# emergency-button.net
KiCad netlist of a schematic drawn in EasyEDA Pro
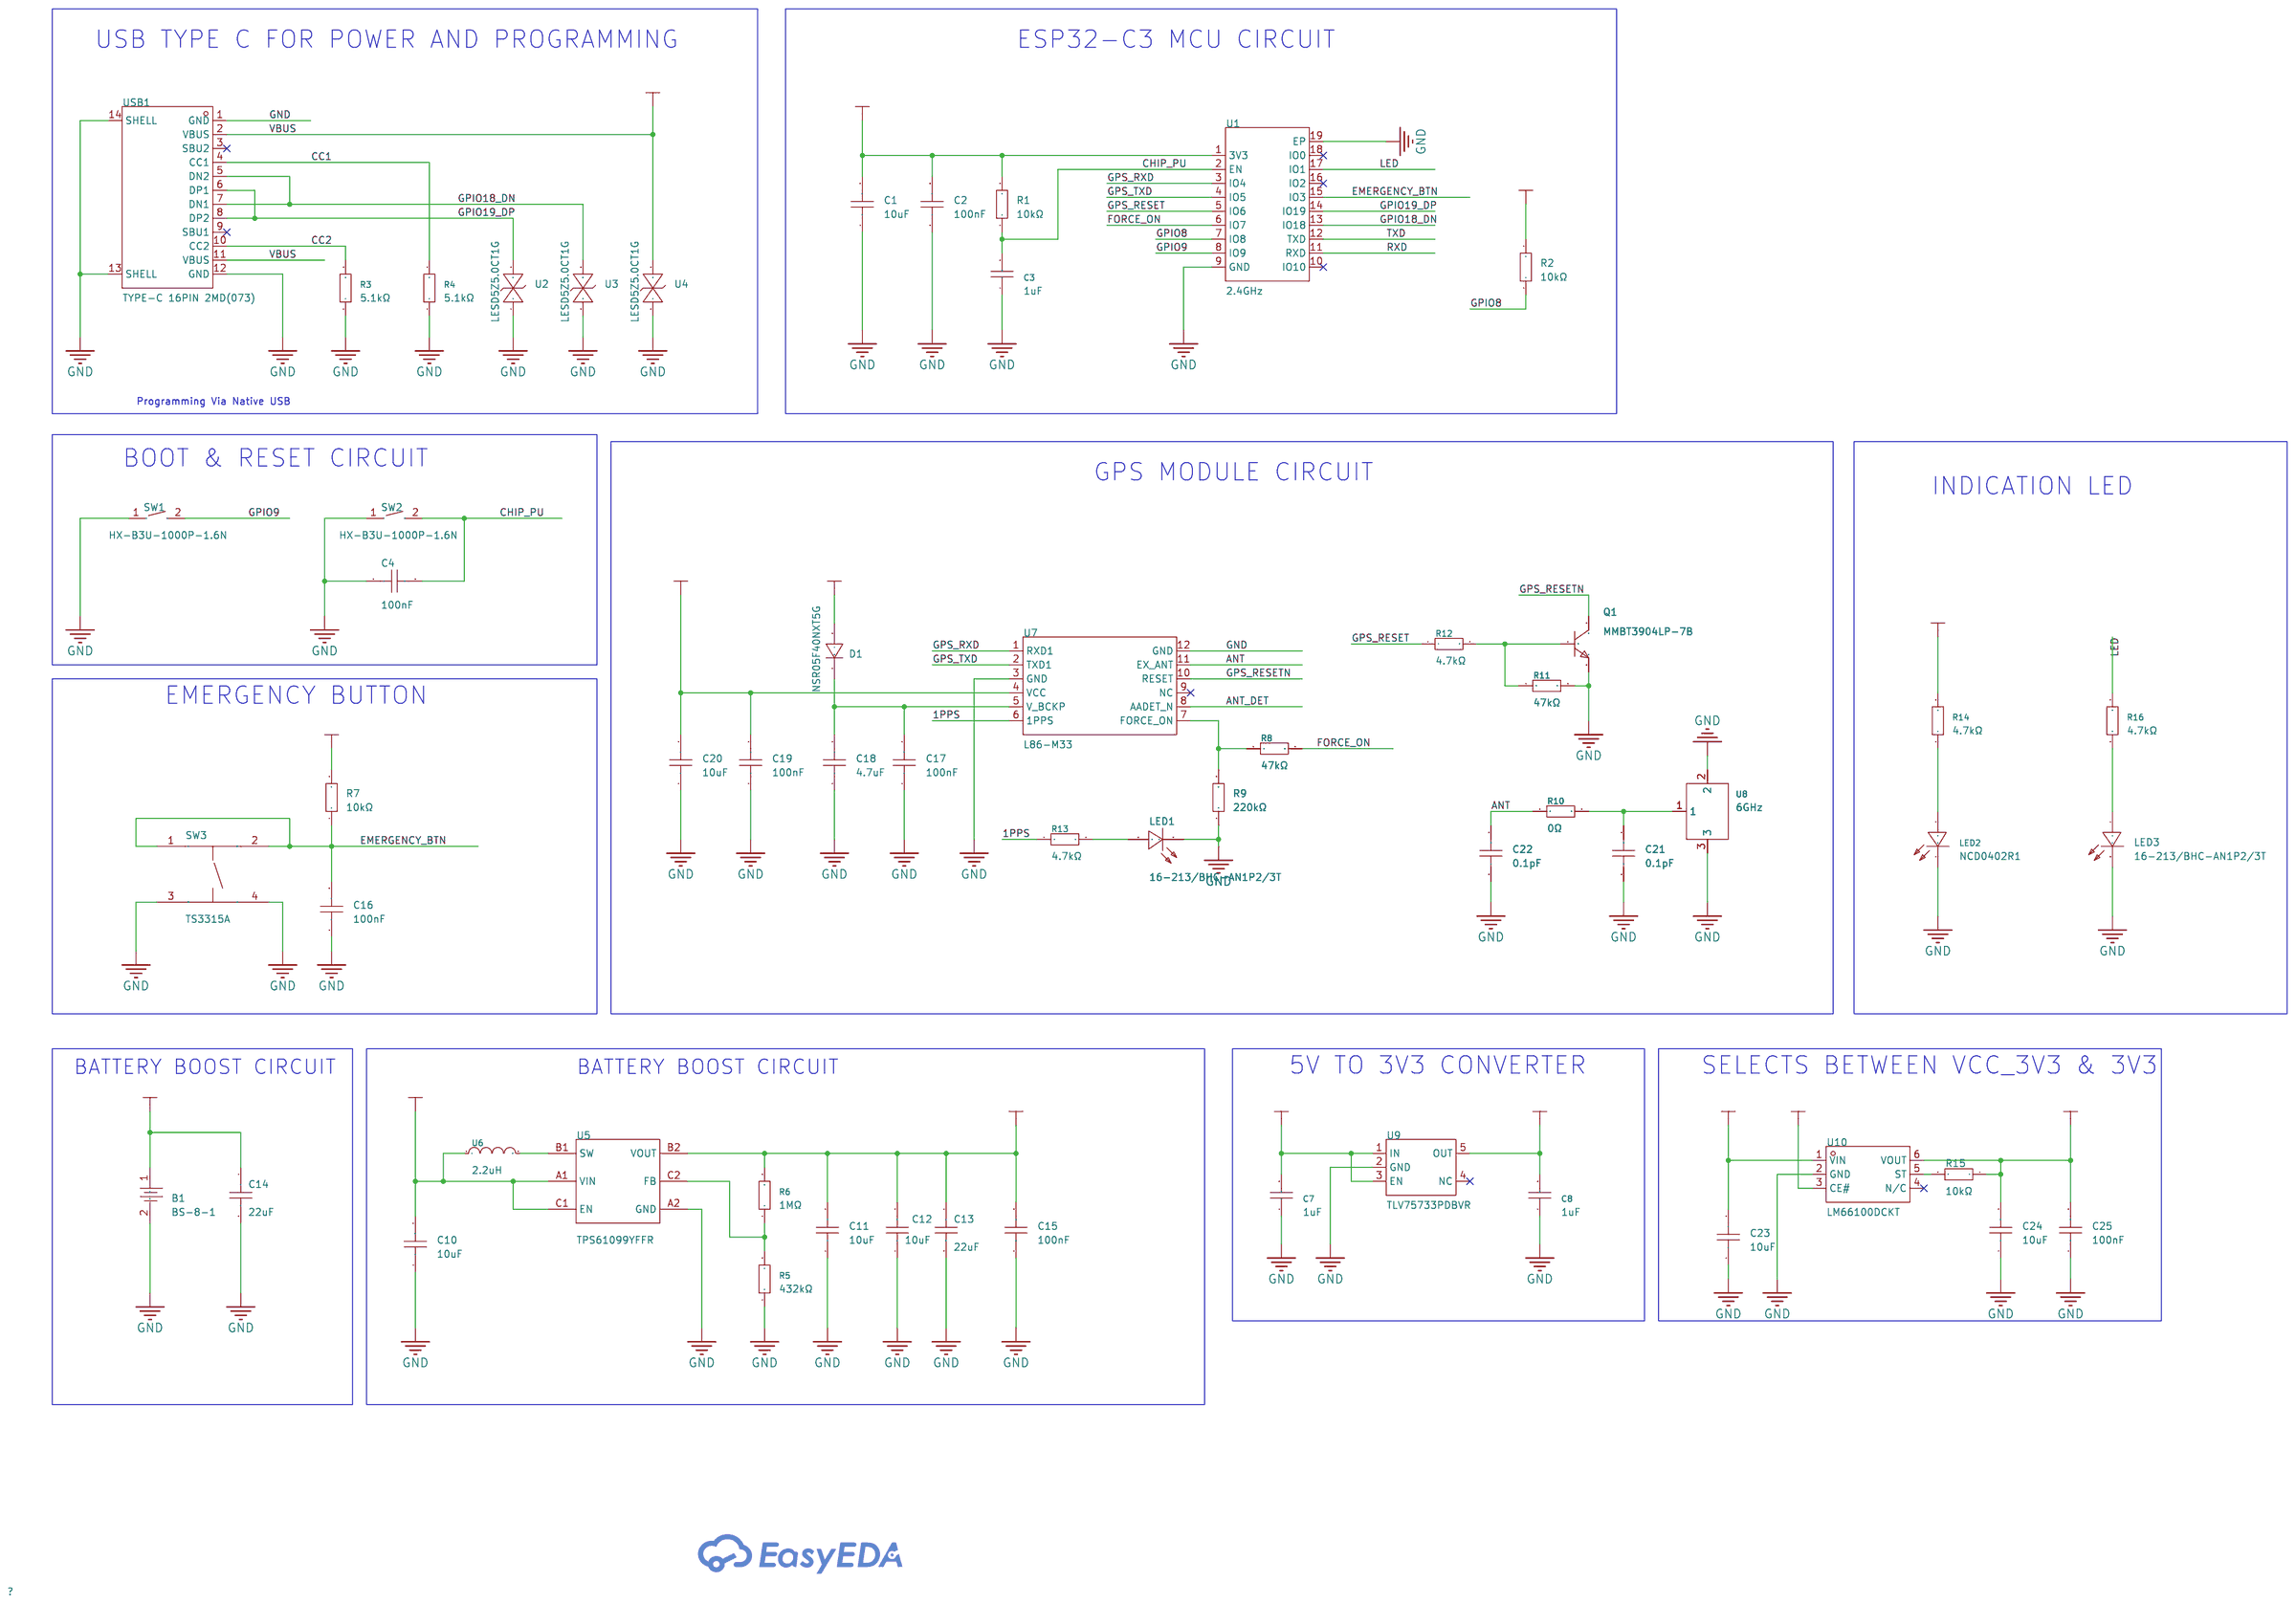
[diagram p0: schematic sheet]

(export (version "E")
  (design (tool "Eeschema 10.0.6"))
  (components
    (comp (ref "B1")
      (value "BS-8-1")
      (footprint "easyedapro:BAT-TH_BS-8-1")
      (fields (field (name "Manufacturer") "QIJEY"))
      (libsource (lib "easyedapro") (part "CR2032-BS-8-1"))
    )
    (comp (ref "C1")
      (value "10uF")
      (footprint "easyedapro:C0402")
      (description "Capacitance:10uF Tolerance:±20% Tolerance:±20% Voltage Rating:10V Temperature Coefficient:X5R")
      (fields
        (field (name "Manufacturer Part") "CL05A106MP5NUNC")
        (field (name "Manufacturer") "SAMSUNG(三星)")
      )
      (libsource (lib "easyedapro") (part "CL05A106MP5NUNC_C315248"))
    )
    (comp (ref "C2")
      (value "100nF")
      (footprint "easyedapro:C0402")
      (description "Capacitance:100nF Tolerance:±10% Tolerance:±10% Voltage Rating:50V Temperature Coefficient:X7R")
      (fields
        (field (name "Manufacturer Part") "CL05B104KB54PNC")
        (field (name "Manufacturer") "SAMSUNG(三星)")
      )
      (libsource (lib "easyedapro") (part "CL05B104KB54PNC"))
    )
    (comp (ref "C3")
      (value "1uF")
      (footprint "easyedapro:C0402")
      (description "Capacitance:1uF Tolerance:±10% Tolerance:±10% Voltage Rating:16V Temperature Coefficient:X5R")
      (fields
        (field (name "Manufacturer Part") "CL05A105KO5NNNC")
        (field (name "Manufacturer") "SAMSUNG(三星)")
      )
      (libsource (lib "easyedapro") (part "CL05A105KO5NNNC"))
    )
    (comp (ref "C4")
      (value "100nF")
      (footprint "easyedapro:C0402")
      (description "Capacitance:100nF Tolerance:±10% Tolerance:±10% Voltage Rating:50V Temperature Coefficient:X7R")
      (fields
        (field (name "Manufacturer Part") "CL05B104KB54PNC")
        (field (name "Manufacturer") "SAMSUNG(三星)")
      )
      (libsource (lib "easyedapro") (part "CL05B104KB54PNC"))
    )
    (comp (ref "C7")
      (value "1uF")
      (footprint "easyedapro:C0402")
      (description "Capacitance:1uF Tolerance:±10% Tolerance:±10% Voltage Rating:16V Temperature Coefficient:X5R")
      (fields
        (field (name "Manufacturer Part") "CL05A105KO5NNNC")
        (field (name "Manufacturer") "SAMSUNG(三星)")
      )
      (libsource (lib "easyedapro") (part "CL05A105KO5NNNC"))
    )
    (comp (ref "C8")
      (value "1uF")
      (footprint "easyedapro:C0402")
      (description "Capacitance:1uF Tolerance:±10% Tolerance:±10% Voltage Rating:16V Temperature Coefficient:X5R")
      (fields
        (field (name "Manufacturer Part") "CL05A105KO5NNNC")
        (field (name "Manufacturer") "SAMSUNG(三星)")
      )
      (libsource (lib "easyedapro") (part "CL05A105KO5NNNC"))
    )
    (comp (ref "C10")
      (value "10uF")
      (footprint "easyedapro:C0402")
      (description "Capacitance:10uF Tolerance:±20% Tolerance:±20% Voltage Rating:10V Temperature Coefficient:X5R")
      (fields
        (field (name "Manufacturer Part") "CL05A106MP5NUNC")
        (field (name "Manufacturer") "SAMSUNG(三星)")
      )
      (libsource (lib "easyedapro") (part "CL05A106MP5NUNC_C315248"))
    )
    (comp (ref "C11")
      (value "10uF")
      (footprint "easyedapro:C0402")
      (description "Capacitance:10uF Tolerance:±20% Tolerance:±20% Voltage Rating:10V Temperature Coefficient:X5R")
      (fields
        (field (name "Manufacturer Part") "CL05A106MP5NUNC")
        (field (name "Manufacturer") "SAMSUNG(三星)")
      )
      (libsource (lib "easyedapro") (part "CL05A106MP5NUNC_C315248"))
    )
    (comp (ref "C12")
      (value "10uF")
      (footprint "easyedapro:C0402")
      (description "Capacitance:10uF Tolerance:±20% Tolerance:±20% Voltage Rating:10V Temperature Coefficient:X5R")
      (fields
        (field (name "Manufacturer Part") "CL05A106MP5NUNC")
        (field (name "Manufacturer") "SAMSUNG(三星)")
      )
      (libsource (lib "easyedapro") (part "CL05A106MP5NUNC_C315248"))
    )
    (comp (ref "C13")
      (value "22uF")
      (footprint "easyedapro:C0603")
      (description "Capacitance:22uF Tolerance:±20% Tolerance:±20% Voltage Rating:16V Temperature Coefficient:X5R")
      (fields
        (field (name "Manufacturer Part") "CL10A226MO7JZNC")
        (field (name "Manufacturer") "SAMSUNG(三星)")
      )
      (libsource (lib "easyedapro") (part "CL10A226MO7JZNC"))
    )
    (comp (ref "C14")
      (value "22uF")
      (footprint "easyedapro:C0603")
      (description "Capacitance:22uF Tolerance:±20% Tolerance:±20% Voltage Rating:16V Temperature Coefficient:X5R")
      (fields
        (field (name "Manufacturer Part") "CL10A226MO7JZNC")
        (field (name "Manufacturer") "SAMSUNG(三星)")
      )
      (libsource (lib "easyedapro") (part "CL10A226MO7JZNC"))
    )
    (comp (ref "C15")
      (value "100nF")
      (footprint "easyedapro:C0402")
      (description "Capacitance:100nF Tolerance:±10% Tolerance:±10% Voltage Rating:50V Temperature Coefficient:X7R")
      (fields
        (field (name "Manufacturer Part") "CL05B104KB54PNC")
        (field (name "Manufacturer") "SAMSUNG(三星)")
      )
      (libsource (lib "easyedapro") (part "CL05B104KB54PNC"))
    )
    (comp (ref "C16")
      (value "100nF")
      (footprint "easyedapro:C0402")
      (description "Capacitance:100nF Tolerance:±10% Tolerance:±10% Voltage Rating:50V Temperature Coefficient:X7R")
      (fields
        (field (name "Manufacturer Part") "CL05B104KB54PNC")
        (field (name "Manufacturer") "SAMSUNG(三星)")
      )
      (libsource (lib "easyedapro") (part "CL05B104KB54PNC"))
    )
    (comp (ref "C17")
      (value "100nF")
      (footprint "easyedapro:C0402")
      (description "Capacitance:100nF Tolerance:±10% Tolerance:±10% Voltage Rating:50V Temperature Coefficient:X7R")
      (fields
        (field (name "Manufacturer Part") "CL05B104KB54PNC")
        (field (name "Manufacturer") "SAMSUNG(三星)")
      )
      (libsource (lib "easyedapro") (part "CL05B104KB54PNC"))
    )
    (comp (ref "C18")
      (value "4.7uF")
      (footprint "easyedapro:C0402")
      (description "Capacitance:4.7uF Tolerance:±20% Tolerance:±20% Voltage Rating:10V Temperature Coefficient:X5R")
      (fields
        (field (name "Manufacturer Part") "CL05A475MP5NRNC")
        (field (name "Manufacturer") "SAMSUNG(三星)")
      )
      (libsource (lib "easyedapro") (part "CL05A475MP5NRNC"))
    )
    (comp (ref "C19")
      (value "100nF")
      (footprint "easyedapro:C0402")
      (description "Capacitance:100nF Tolerance:±10% Tolerance:±10% Voltage Rating:50V Temperature Coefficient:X7R")
      (fields
        (field (name "Manufacturer Part") "CL05B104KB54PNC")
        (field (name "Manufacturer") "SAMSUNG(三星)")
      )
      (libsource (lib "easyedapro") (part "CL05B104KB54PNC"))
    )
    (comp (ref "C20")
      (value "10uF")
      (footprint "easyedapro:C0402")
      (description "Capacitance:10uF Tolerance:±20% Tolerance:±20% Voltage Rating:10V Temperature Coefficient:X5R")
      (fields
        (field (name "Manufacturer Part") "CL05A106MP5NUNC")
        (field (name "Manufacturer") "SAMSUNG(三星)")
      )
      (libsource (lib "easyedapro") (part "CL05A106MP5NUNC_C315248"))
    )
    (comp (ref "C21")
      (value "0.1pF")
      (footprint "easyedapro:C0402")
      (description "Capacitance:0.1pF Voltage Rating:50V Temperature Coefficient:C0G")
      (fields
        (field (name "Manufacturer Part") "GJM1555C1HR10WB01D")
        (field (name "Manufacturer") "muRata(村田)")
      )
      (libsource (lib "easyedapro") (part "GJM1555C1HR10WB01D"))
    )
    (comp (ref "C22")
      (value "0.1pF")
      (footprint "easyedapro:C0402")
      (description "Capacitance:0.1pF Voltage Rating:50V Temperature Coefficient:C0G")
      (fields
        (field (name "Manufacturer Part") "GJM1555C1HR10WB01D")
        (field (name "Manufacturer") "muRata(村田)")
      )
      (libsource (lib "easyedapro") (part "GJM1555C1HR10WB01D"))
    )
    (comp (ref "C23")
      (value "10uF")
      (footprint "easyedapro:C0402")
      (description "Capacitance:10uF Tolerance:±20% Tolerance:±20% Voltage Rating:10V Temperature Coefficient:X5R")
      (fields
        (field (name "Manufacturer Part") "CL05A106MP5NUNC")
        (field (name "Manufacturer") "SAMSUNG(三星)")
      )
      (libsource (lib "easyedapro") (part "CL05A106MP5NUNC_C315248"))
    )
    (comp (ref "C24")
      (value "10uF")
      (footprint "easyedapro:C0402")
      (description "Capacitance:10uF Tolerance:±20% Tolerance:±20% Voltage Rating:10V Temperature Coefficient:X5R")
      (fields
        (field (name "Manufacturer Part") "CL05A106MP5NUNC")
        (field (name "Manufacturer") "SAMSUNG(三星)")
      )
      (libsource (lib "easyedapro") (part "CL05A106MP5NUNC_C315248"))
    )
    (comp (ref "C25")
      (value "100nF")
      (footprint "easyedapro:C0402")
      (description "Capacitance:100nF Tolerance:±10% Tolerance:±10% Voltage Rating:50V Temperature Coefficient:X7R")
      (fields
        (field (name "Manufacturer Part") "CL05B104KB54PNC")
        (field (name "Manufacturer") "SAMSUNG(三星)")
      )
      (libsource (lib "easyedapro") (part "CL05B104KB54PNC"))
    )
    (comp (ref "D1")
      (value "NSR05F40NXT5G")
      (footprint "easyedapro:DSN2_L1.0-W0.6-RD")
      (fields (field (name "Manufacturer") "onsemi(安森美)"))
      (libsource (lib "easyedapro") (part "NSR05F40NXT5G"))
    )
    (comp (ref "LED1")
      (value "16-213/BHC-AN1P2/3T")
      (footprint "easyedapro:LED0402-R-RD")
      (description "Illumination Color:Blue")
      (fields (field (name "Manufacturer") "EVERLIGHT(亿光)"))
      (libsource (lib "easyedapro") (part "16-213/BHC-AN1P2/3T"))
    )
    (comp (ref "LED2")
      (value "NCD0402R1")
      (footprint "easyedapro:LED0402-RD")
      (fields (field (name "Manufacturer") "国星光电"))
      (libsource (lib "easyedapro") (part "FC-F1005HRK-620H5"))
    )
    (comp (ref "LED3")
      (value "16-213/BHC-AN1P2/3T")
      (footprint "easyedapro:LED0402-R-RD")
      (description "Illumination Color:Blue")
      (fields (field (name "Manufacturer") "EVERLIGHT(亿光)"))
      (libsource (lib "easyedapro") (part "16-213/BHC-AN1P2/3T"))
    )
    (comp (ref "Q1")
      (value "MMBT3904LP-7B")
      (footprint "easyedapro:X1-DFN1006-3_L1.0-W0.6-BR")
      (fields (field (name "Manufacturer") "DIODES(美台)"))
      (libsource (lib "easyedapro") (part "MMBT3904LP-7B"))
    )
    (comp (ref "R1")
      (value "10kΩ")
      (footprint "easyedapro:R0402")
      (fields
        (field (name "Manufacturer Part") "0402WGF1002TCE")
        (field (name "Manufacturer") "UNI-ROYAL(厚声)")
      )
      (libsource (lib "easyedapro") (part "0402WGF1002TCE"))
    )
    (comp (ref "R2")
      (value "10kΩ")
      (footprint "easyedapro:R0402")
      (fields
        (field (name "Manufacturer Part") "0402WGF1002TCE")
        (field (name "Manufacturer") "UNI-ROYAL(厚声)")
      )
      (libsource (lib "easyedapro") (part "0402WGF1002TCE"))
    )
    (comp (ref "R3")
      (value "5.1kΩ")
      (footprint "easyedapro:R0402")
      (fields
        (field (name "Manufacturer Part") "0402WGF5101TCE")
        (field (name "Manufacturer") "UNI-ROYAL(厚声)")
      )
      (libsource (lib "easyedapro") (part "0402WGF5101TCE"))
    )
    (comp (ref "R4")
      (value "5.1kΩ")
      (footprint "easyedapro:R0402")
      (fields
        (field (name "Manufacturer Part") "0402WGF5101TCE")
        (field (name "Manufacturer") "UNI-ROYAL(厚声)")
      )
      (libsource (lib "easyedapro") (part "0402WGF5101TCE"))
    )
    (comp (ref "R5")
      (value "432kΩ")
      (footprint "easyedapro:R0402")
      (fields
        (field (name "Manufacturer Part") "0402WGF4323TCE")
        (field (name "Manufacturer") "UNI-ROYAL(厚声)")
      )
      (libsource (lib "easyedapro") (part "0402WGF4323TCE"))
    )
    (comp (ref "R6")
      (value "1MΩ")
      (footprint "easyedapro:R0402")
      (fields
        (field (name "Manufacturer Part") "0402WGF1004TCE")
        (field (name "Manufacturer") "UNI-ROYAL(厚声)")
      )
      (libsource (lib "easyedapro") (part "0402WGF1004TCE"))
    )
    (comp (ref "R7")
      (value "10kΩ")
      (footprint "easyedapro:R0402")
      (fields
        (field (name "Manufacturer Part") "0402WGF1002TCE")
        (field (name "Manufacturer") "UNI-ROYAL(厚声)")
      )
      (libsource (lib "easyedapro") (part "0402WGF1002TCE"))
    )
    (comp (ref "R8")
      (value "47kΩ")
      (footprint "easyedapro:R0402")
      (fields
        (field (name "Manufacturer Part") "0402WGJ0473TCE")
        (field (name "Manufacturer") "UNI-ROYAL(厚声)")
      )
      (libsource (lib "easyedapro") (part "0402WGJ0473TCE"))
    )
    (comp (ref "R9")
      (value "220kΩ")
      (footprint "easyedapro:R0402")
      (fields
        (field (name "Manufacturer Part") "0402WGF2203TCE")
        (field (name "Manufacturer") "UNI-ROYAL(厚声)")
      )
      (libsource (lib "easyedapro") (part "0402WGF2203TCE"))
    )
    (comp (ref "R10")
      (value "0Ω")
      (footprint "easyedapro:R0402")
      (fields
        (field (name "Manufacturer Part") "0402WGF0000TCE")
        (field (name "Manufacturer") "UNI-ROYAL(厚声)")
      )
      (libsource (lib "easyedapro") (part "0402WGF0000TCE"))
    )
    (comp (ref "R11")
      (value "47kΩ")
      (footprint "easyedapro:R0402")
      (fields
        (field (name "Manufacturer Part") "0402WGJ0473TCE")
        (field (name "Manufacturer") "UNI-ROYAL(厚声)")
      )
      (libsource (lib "easyedapro") (part "0402WGJ0473TCE"))
    )
    (comp (ref "R12")
      (value "4.7kΩ")
      (footprint "easyedapro:R0402")
      (fields
        (field (name "Manufacturer Part") "0402WGF4701TCE")
        (field (name "Manufacturer") "UNI-ROYAL(厚声)")
      )
      (libsource (lib "easyedapro") (part "0402WGF4701TCE"))
    )
    (comp (ref "R13")
      (value "4.7kΩ")
      (footprint "easyedapro:R0402")
      (fields
        (field (name "Manufacturer Part") "0402WGF4701TCE")
        (field (name "Manufacturer") "UNI-ROYAL(厚声)")
      )
      (libsource (lib "easyedapro") (part "0402WGF4701TCE"))
    )
    (comp (ref "R14")
      (value "4.7kΩ")
      (footprint "easyedapro:R0402")
      (fields
        (field (name "Manufacturer Part") "0402WGF4701TCE")
        (field (name "Manufacturer") "UNI-ROYAL(厚声)")
      )
      (libsource (lib "easyedapro") (part "0402WGF4701TCE"))
    )
    (comp (ref "R15")
      (value "10kΩ")
      (footprint "easyedapro:R0402")
      (fields
        (field (name "Manufacturer Part") "0402WGF1002TCE")
        (field (name "Manufacturer") "UNI-ROYAL(厚声)")
      )
      (libsource (lib "easyedapro") (part "0402WGF1002TCE"))
    )
    (comp (ref "R16")
      (value "4.7kΩ")
      (footprint "easyedapro:R0402")
      (fields
        (field (name "Manufacturer Part") "0402WGF4701TCE")
        (field (name "Manufacturer") "UNI-ROYAL(厚声)")
      )
      (libsource (lib "easyedapro") (part "0402WGF4701TCE"))
    )
    (comp (ref "SW1")
      (value "HX-B3U-1000P-1.6N")
      (footprint "easyedapro:SW-SMD_2P-L3.0-W2.5-LS4.0")
      (fields (field (name "Manufacturer") "hanxia(韩下)"))
      (libsource (lib "easyedapro") (part "HX-B3U-1000P-1.6N"))
    )
    (comp (ref "SW2")
      (value "HX-B3U-1000P-1.6N")
      (footprint "easyedapro:SW-SMD_2P-L3.0-W2.5-LS4.0")
      (fields (field (name "Manufacturer") "hanxia(韩下)"))
      (libsource (lib "easyedapro") (part "HX-B3U-1000P-1.6N"))
    )
    (comp (ref "SW3")
      (value "TS3315A")
      (footprint "easyedapro:SW-SMD_4P-L3.4-W3.4-P2.00-LS4.0")
      (fields (field (name "Manufacturer") "SHOU HAN(首韩)"))
      (libsource (lib "easyedapro") (part "TS3315A"))
    )
    (comp (ref "U1")
      (value "2.4GHz")
      (footprint "easyedapro:BULETM-SMD_ESPRESSIF_ESP32-C3-WROOM-02-N4-4MB")
      (fields
        (field (name "Manufacturer Part") "ESP32-C3-WROOM-02-N4")
        (field (name "Manufacturer") "ESPRESSIF(乐鑫)")
      )
      (libsource (lib "easyedapro") (part "ESP32-C3-WROOM-02-N4(4MB)"))
    )
    (comp (ref "U2")
      (value "LESD5Z5.0CT1G")
      (footprint "easyedapro:SOD-523_L1.2-W0.8-LS1.6-BI")
      (fields (field (name "Manufacturer") "HXY MOSFET(华轩阳电子)"))
      (libsource (lib "easyedapro") (part "LESD5Z5.0CT1G_C5451650"))
    )
    (comp (ref "U3")
      (value "LESD5Z5.0CT1G")
      (footprint "easyedapro:SOD-523_L1.2-W0.8-LS1.6-BI")
      (fields (field (name "Manufacturer") "HXY MOSFET(华轩阳电子)"))
      (libsource (lib "easyedapro") (part "LESD5Z5.0CT1G_C5451650"))
    )
    (comp (ref "U4")
      (value "LESD5Z5.0CT1G")
      (footprint "easyedapro:SOD-523_L1.2-W0.8-LS1.6-BI")
      (fields (field (name "Manufacturer") "HXY MOSFET(华轩阳电子)"))
      (libsource (lib "easyedapro") (part "LESD5Z5.0CT1G_C5451650"))
    )
    (comp (ref "U5")
      (value "TPS61099YFFR")
      (footprint "easyedapro:DSBGA-6_L0.8-W1.2-P0.40-R3-C2-TL")
      (fields (field (name "Manufacturer") "TI(德州仪器)"))
      (libsource (lib "easyedapro") (part "TPS61099YFFR"))
    )
    (comp (ref "U6")
      (value "2.2uH")
      (footprint "easyedapro:IND-SMD_L2.0-W1.6")
      (fields (field (name "Manufacturer Part") "VLS201610CX-2R2M-1") (field (name "Manufacturer") "TDK"))
      (libsource (lib "easyedapro") (part "VLS201610CX-2R2M-1"))
    )
    (comp (ref "U7")
      (value "L86-M33")
      (footprint "easyedapro:GPSM-SMD_12P-L16.0-W16.0-P2.54-BL")
      (fields (field (name "Manufacturer") "Quectel(移远)"))
      (libsource (lib "easyedapro") (part "L86-M33"))
    )
    (comp (ref "U8")
      (value "6GHz")
      (footprint "easyedapro:IPEX-SMD_BWIPX-1-001E")
      (fields
        (field (name "Manufacturer Part") "BWU.FL-IPEX1")
        (field (name "Manufacturer") "BAT WIRELESS(蝙蝠无线)")
      )
      (libsource (lib "easyedapro") (part "BWU.FL-IPEX1"))
    )
    (comp (ref "U9")
      (value "TLV75733PDBVR")
      (footprint "easyedapro:SOT-23-5_L2.9-W1.6-P0.95-LS2.8-BL")
      (fields (field (name "Manufacturer") "TI(德州仪器)"))
      (libsource (lib "easyedapro") (part "TLV75733PDBVR"))
    )
    (comp (ref "U10")
      (value "LM66100DCKT")
      (footprint "easyedapro:SC-70-6_L2.0-W1.3-P0.65-LS2.1-BL")
      (fields (field (name "Manufacturer") "TI(德州仪器)"))
      (libsource (lib "easyedapro") (part "LM66100DCKT"))
    )
    (comp (ref "USB1")
      (value "TYPE-C 16PIN 2MD(073)")
      (footprint "easyedapro:USB-C-SMD_TYPE-C-6PIN-2MD-073")
      (fields (field (name "Manufacturer") "SHOU HAN(首韩)"))
      (libsource (lib "easyedapro") (part "TYPE-C 16PIN 2MD(073)"))
    )
  )
  (nets
    (net (code "1") (name "/1PPS") (class "Default")
      (node (ref "R13") (pin "1") (pinfunction "1_1") (pintype "input"))
      (node (ref "U7") (pin "6") (pinfunction "1PPS_6") (pintype "unspecified"))
    )
    (net (code "2") (name "/ANT") (class "Default")
      (node (ref "C22") (pin "1") (pinfunction "1_1") (pintype "unspecified"))
      (node (ref "R10") (pin "1") (pinfunction "1_1") (pintype "input"))
      (node (ref "U7") (pin "11") (pinfunction "EX_ANT_11") (pintype "unspecified"))
    )
    (net (code "3") (name "/ANT_DET") (class "Default")
      (node (ref "U7") (pin "8") (pinfunction "AADET_N_8") (pintype "unspecified"))
    )
    (net (code "4") (name "/CC1") (class "Default")
      (node (ref "R4") (pin "2") (pinfunction "2_2") (pintype "input"))
      (node (ref "USB1") (pin "4") (pinfunction "CC1_4") (pintype "unspecified"))
    )
    (net (code "5") (name "/CC2") (class "Default")
      (node (ref "R3") (pin "2") (pinfunction "2_2") (pintype "input"))
      (node (ref "USB1") (pin "10") (pinfunction "CC2_10") (pintype "unspecified"))
    )
    (net (code "6") (name "/CHIP_PU") (class "Default")
      (node (ref "C3") (pin "2") (pinfunction "2_2") (pintype "input"))
      (node (ref "C4") (pin "2") (pinfunction "2_2") (pintype "input"))
      (node (ref "R1") (pin "1") (pinfunction "1_1") (pintype "input"))
      (node (ref "SW2") (pin "2") (pinfunction "2_2") (pintype "unspecified"))
      (node (ref "U1") (pin "2") (pinfunction "EN_2") (pintype "unspecified"))
    )
    (net (code "7") (name "/EMERGENCY_BTN") (class "Default")
      (node (ref "C16") (pin "2") (pinfunction "2_2") (pintype "input"))
      (node (ref "R7") (pin "1") (pinfunction "1_1") (pintype "input"))
      (node (ref "SW3") (pin "1") (pinfunction "A_1") (pintype "unspecified"))
      (node (ref "SW3") (pin "2") (pinfunction "B_2") (pintype "unspecified"))
      (node (ref "U1") (pin "15") (pinfunction "IO3_15") (pintype "unspecified"))
    )
    (net (code "8") (name "/FORCE_ON") (class "Default")
      (node (ref "R8") (pin "2") (pinfunction "2_2") (pintype "input"))
      (node (ref "U1") (pin "6") (pinfunction "IO7_6") (pintype "unspecified"))
    )
    (net (code "9") (name "/GPIO8") (class "Default")
      (node (ref "R2") (pin "1") (pinfunction "1_1") (pintype "input"))
      (node (ref "U1") (pin "7") (pinfunction "IO8_7") (pintype "unspecified"))
    )
    (net (code "10") (name "/GPIO9") (class "Default")
      (node (ref "SW1") (pin "2") (pinfunction "2_2") (pintype "unspecified"))
      (node (ref "U1") (pin "8") (pinfunction "IO9_8") (pintype "unspecified"))
    )
    (net (code "11") (name "/GPIO18_DN") (class "Default")
      (node (ref "U1") (pin "13") (pinfunction "IO18_13") (pintype "unspecified"))
      (node (ref "U3") (pin "2") (pinfunction "2_2") (pintype "unspecified"))
      (node (ref "USB1") (pin "5") (pinfunction "DN2_5") (pintype "unspecified"))
      (node (ref "USB1") (pin "7") (pinfunction "DN1_7") (pintype "unspecified"))
    )
    (net (code "12") (name "/GPIO19_DP") (class "Default")
      (node (ref "U1") (pin "14") (pinfunction "IO19_14") (pintype "unspecified"))
      (node (ref "U2") (pin "2") (pinfunction "2_2") (pintype "unspecified"))
      (node (ref "USB1") (pin "6") (pinfunction "DP1_6") (pintype "unspecified"))
      (node (ref "USB1") (pin "8") (pinfunction "DP2_8") (pintype "unspecified"))
    )
    (net (code "13") (name "/GPS_RESET") (class "Default")
      (node (ref "R12") (pin "1") (pinfunction "1_1") (pintype "input"))
      (node (ref "U1") (pin "5") (pinfunction "IO6_5") (pintype "unspecified"))
    )
    (net (code "14") (name "/GPS_RESETN") (class "Default")
      (node (ref "Q1") (pin "3") (pinfunction "C_3") (pintype "unspecified"))
      (node (ref "U7") (pin "10") (pinfunction "RESET_10") (pintype "unspecified"))
    )
    (net (code "15") (name "/GPS_RXD") (class "Default")
      (node (ref "U1") (pin "3") (pinfunction "IO4_3") (pintype "unspecified"))
      (node (ref "U7") (pin "1") (pinfunction "RXD1_1") (pintype "unspecified"))
    )
    (net (code "16") (name "/GPS_TXD") (class "Default")
      (node (ref "U1") (pin "4") (pinfunction "IO5_4") (pintype "unspecified"))
      (node (ref "U7") (pin "2") (pinfunction "TXD1_2") (pintype "unspecified"))
    )
    (net (code "17") (name "/LED") (class "Default")
      (node (ref "R16") (pin "1") (pinfunction "1_1") (pintype "input"))
      (node (ref "U1") (pin "17") (pinfunction "IO1_17") (pintype "unspecified"))
    )
    (net (code "18") (name "/RXD") (class "Default")
      (node (ref "U1") (pin "11") (pinfunction "RXD_11") (pintype "unspecified"))
    )
    (net (code "19") (name "/TXD") (class "Default")
      (node (ref "U1") (pin "12") (pinfunction "TXD_12") (pintype "unspecified"))
    )
    (net (code "20") (name "3V3") (class "Default")
      (node (ref "C1") (pin "2") (pinfunction "2_2") (pintype "unspecified"))
      (node (ref "C11") (pin "2") (pinfunction "2_2") (pintype "unspecified"))
      (node (ref "C12") (pin "2") (pinfunction "2_2") (pintype "unspecified"))
      (node (ref "C13") (pin "1") (pinfunction "1_1") (pintype "unspecified"))
      (node (ref "C15") (pin "2") (pinfunction "2_2") (pintype "input"))
      (node (ref "C19") (pin "2") (pinfunction "2_2") (pintype "input"))
      (node (ref "C2") (pin "2") (pinfunction "2_2") (pintype "input"))
      (node (ref "C20") (pin "2") (pinfunction "2_2") (pintype "unspecified"))
      (node (ref "C24") (pin "2") (pinfunction "2_2") (pintype "unspecified"))
      (node (ref "C25") (pin "2") (pinfunction "2_2") (pintype "input"))
      (node (ref "D1") (pin "2") (pinfunction "A_2") (pintype "unspecified"))
      (node (ref "R1") (pin "2") (pinfunction "2_2") (pintype "input"))
      (node (ref "R15") (pin "1") (pinfunction "1_1") (pintype "input"))
      (node (ref "R2") (pin "2") (pinfunction "2_2") (pintype "input"))
      (node (ref "R6") (pin "2") (pinfunction "2_2") (pintype "input"))
      (node (ref "R7") (pin "2") (pinfunction "2_2") (pintype "input"))
      (node (ref "U1") (pin "1") (pinfunction "3V3_1") (pintype "unspecified"))
      (node (ref "U10") (pin "3") (pinfunction "CE#_3") (pintype "input"))
      (node (ref "U10") (pin "6") (pinfunction "VOUT_6") (pintype "input"))
      (node (ref "U5") (pin "B2") (pinfunction "VOUT_B2") (pintype "unspecified"))
      (node (ref "U7") (pin "4") (pinfunction "VCC_4") (pintype "unspecified"))
    )
    (net (code "21") (name "BAT+") (class "Default")
      (node (ref "B1") (pin "1") (pinfunction "1_1") (pintype "input"))
      (node (ref "C10") (pin "2") (pinfunction "2_2") (pintype "unspecified"))
      (node (ref "C14") (pin "1") (pinfunction "1_1") (pintype "unspecified"))
      (node (ref "U5") (pin "A1") (pinfunction "VIN_A1") (pintype "unspecified"))
      (node (ref "U5") (pin "C1") (pinfunction "EN_C1") (pintype "unspecified"))
      (node (ref "U6") (pin "1") (pinfunction "1_1") (pintype "input"))
    )
    (net (code "22") (name "GND") (class "Default")
      (node (ref "B1") (pin "2") (pinfunction "2_2") (pintype "input"))
      (node (ref "C1") (pin "1") (pinfunction "1_1") (pintype "unspecified"))
      (node (ref "C10") (pin "1") (pinfunction "1_1") (pintype "unspecified"))
      (node (ref "C11") (pin "1") (pinfunction "1_1") (pintype "unspecified"))
      (node (ref "C12") (pin "1") (pinfunction "1_1") (pintype "unspecified"))
      (node (ref "C13") (pin "2") (pinfunction "2_2") (pintype "unspecified"))
      (node (ref "C14") (pin "2") (pinfunction "2_2") (pintype "unspecified"))
      (node (ref "C15") (pin "1") (pinfunction "1_1") (pintype "input"))
      (node (ref "C16") (pin "1") (pinfunction "1_1") (pintype "input"))
      (node (ref "C17") (pin "1") (pinfunction "1_1") (pintype "input"))
      (node (ref "C18") (pin "1") (pinfunction "1_1") (pintype "unspecified"))
      (node (ref "C19") (pin "1") (pinfunction "1_1") (pintype "input"))
      (node (ref "C2") (pin "1") (pinfunction "1_1") (pintype "input"))
      (node (ref "C20") (pin "1") (pinfunction "1_1") (pintype "unspecified"))
      (node (ref "C21") (pin "2") (pinfunction "2_2") (pintype "unspecified"))
      (node (ref "C22") (pin "2") (pinfunction "2_2") (pintype "unspecified"))
      (node (ref "C23") (pin "1") (pinfunction "1_1") (pintype "unspecified"))
      (node (ref "C24") (pin "1") (pinfunction "1_1") (pintype "unspecified"))
      (node (ref "C25") (pin "1") (pinfunction "1_1") (pintype "input"))
      (node (ref "C3") (pin "1") (pinfunction "1_1") (pintype "input"))
      (node (ref "C4") (pin "1") (pinfunction "1_1") (pintype "input"))
      (node (ref "C7") (pin "1") (pinfunction "1_1") (pintype "input"))
      (node (ref "C8") (pin "1") (pinfunction "1_1") (pintype "input"))
      (node (ref "LED1") (pin "2") (pinfunction "K_2") (pintype "unspecified"))
      (node (ref "LED2") (pin "1") (pinfunction "K_1") (pintype "input"))
      (node (ref "LED3") (pin "2") (pinfunction "K_2") (pintype "unspecified"))
      (node (ref "Q1") (pin "2") (pinfunction "E_2") (pintype "unspecified"))
      (node (ref "R11") (pin "2") (pinfunction "2_2") (pintype "input"))
      (node (ref "R3") (pin "1") (pinfunction "1_1") (pintype "input"))
      (node (ref "R4") (pin "1") (pinfunction "1_1") (pintype "input"))
      (node (ref "R5") (pin "1") (pinfunction "1_1") (pintype "input"))
      (node (ref "R9") (pin "1") (pinfunction "1_1") (pintype "input"))
      (node (ref "SW1") (pin "1") (pinfunction "1_1") (pintype "unspecified"))
      (node (ref "SW2") (pin "1") (pinfunction "1_1") (pintype "unspecified"))
      (node (ref "SW3") (pin "3") (pinfunction "C_3") (pintype "unspecified"))
      (node (ref "SW3") (pin "4") (pinfunction "D_4") (pintype "unspecified"))
      (node (ref "U1") (pin "19") (pinfunction "EP_19") (pintype "unspecified"))
      (node (ref "U1") (pin "9") (pinfunction "GND_9") (pintype "unspecified"))
      (node (ref "U10") (pin "2") (pinfunction "GND_2") (pintype "input"))
      (node (ref "U2") (pin "1") (pinfunction "1_1") (pintype "unspecified"))
      (node (ref "U3") (pin "1") (pinfunction "1_1") (pintype "unspecified"))
      (node (ref "U4") (pin "1") (pinfunction "1_1") (pintype "unspecified"))
      (node (ref "U5") (pin "A2") (pinfunction "GND_A2") (pintype "unspecified"))
      (node (ref "U7") (pin "12") (pinfunction "GND_12") (pintype "unspecified"))
      (node (ref "U7") (pin "3") (pinfunction "GND_3") (pintype "unspecified"))
      (node (ref "U8") (pin "2") (pinfunction "2_2") (pintype "input"))
      (node (ref "U8") (pin "3") (pinfunction "3_3") (pintype "input"))
      (node (ref "U9") (pin "2") (pinfunction "GND_2") (pintype "unspecified"))
      (node (ref "USB1") (pin "1") (pinfunction "GND_1") (pintype "unspecified"))
      (node (ref "USB1") (pin "12") (pinfunction "GND_12") (pintype "unspecified"))
      (node (ref "USB1") (pin "13") (pinfunction "SHELL_13") (pintype "unspecified"))
      (node (ref "USB1") (pin "14") (pinfunction "SHELL_14") (pintype "unspecified"))
    )
    (net (code "23") (name "Net-(C21-Pad1)") (class "Default")
      (node (ref "C21") (pin "1") (pinfunction "1_1") (pintype "unspecified"))
      (node (ref "R10") (pin "2") (pinfunction "2_2") (pintype "input"))
      (node (ref "U8") (pin "1") (pinfunction "1_1") (pintype "input"))
    )
    (net (code "24") (name "Net-(D1-C)") (class "Default")
      (node (ref "C17") (pin "2") (pinfunction "2_2") (pintype "input"))
      (node (ref "C18") (pin "2") (pinfunction "2_2") (pintype "unspecified"))
      (node (ref "D1") (pin "1") (pinfunction "C_1") (pintype "unspecified"))
      (node (ref "U7") (pin "5") (pinfunction "V_BCKP_5") (pintype "unspecified"))
    )
    (net (code "25") (name "Net-(LED1-A)") (class "Default")
      (node (ref "LED1") (pin "1") (pinfunction "A_1") (pintype "unspecified"))
      (node (ref "R13") (pin "2") (pinfunction "2_2") (pintype "input"))
    )
    (net (code "26") (name "Net-(LED2-A)") (class "Default")
      (node (ref "LED2") (pin "2") (pinfunction "A_2") (pintype "input"))
      (node (ref "R14") (pin "1") (pinfunction "1_1") (pintype "input"))
    )
    (net (code "27") (name "Net-(LED3-A)") (class "Default")
      (node (ref "LED3") (pin "1") (pinfunction "A_1") (pintype "unspecified"))
      (node (ref "R16") (pin "2") (pinfunction "2_2") (pintype "input"))
    )
    (net (code "28") (name "Net-(Q1-B)") (class "Default")
      (node (ref "Q1") (pin "1") (pinfunction "B_1") (pintype "unspecified"))
      (node (ref "R11") (pin "1") (pinfunction "1_1") (pintype "input"))
      (node (ref "R12") (pin "2") (pinfunction "2_2") (pintype "input"))
    )
    (net (code "29") (name "Net-(U5-FB)") (class "Default")
      (node (ref "R5") (pin "2") (pinfunction "2_2") (pintype "input"))
      (node (ref "R6") (pin "1") (pinfunction "1_1") (pintype "input"))
      (node (ref "U5") (pin "C2") (pinfunction "FB_C2") (pintype "unspecified"))
    )
    (net (code "30") (name "Net-(U5-SW)") (class "Default")
      (node (ref "U5") (pin "B1") (pinfunction "SW_B1") (pintype "unspecified"))
      (node (ref "U6") (pin "2") (pinfunction "2_2") (pintype "input"))
    )
    (net (code "31") (name "Net-(U7-FORCE_ON)") (class "Default")
      (node (ref "R8") (pin "1") (pinfunction "1_1") (pintype "input"))
      (node (ref "R9") (pin "2") (pinfunction "2_2") (pintype "input"))
      (node (ref "U7") (pin "7") (pinfunction "FORCE_ON_7") (pintype "unspecified"))
    )
    (net (code "32") (name "Net-(U10-ST)") (class "Default")
      (node (ref "R15") (pin "2") (pinfunction "2_2") (pintype "input"))
      (node (ref "U10") (pin "5") (pinfunction "ST_5") (pintype "input"))
    )
    (net (code "33") (name "VBUS") (class "Default")
      (node (ref "C7") (pin "2") (pinfunction "2_2") (pintype "input"))
      (node (ref "R14") (pin "2") (pinfunction "2_2") (pintype "input"))
      (node (ref "U4") (pin "2") (pinfunction "2_2") (pintype "unspecified"))
      (node (ref "U9") (pin "1") (pinfunction "IN_1") (pintype "unspecified"))
      (node (ref "U9") (pin "3") (pinfunction "EN_3") (pintype "unspecified"))
      (node (ref "USB1") (pin "11") (pinfunction "VBUS_11") (pintype "unspecified"))
      (node (ref "USB1") (pin "2") (pinfunction "VBUS_2") (pintype "unspecified"))
    )
    (net (code "34") (name "VCC_3V3") (class "Default")
      (node (ref "C23") (pin "2") (pinfunction "2_2") (pintype "unspecified"))
      (node (ref "C8") (pin "2") (pinfunction "2_2") (pintype "input"))
      (node (ref "U10") (pin "1") (pinfunction "VIN_1") (pintype "input"))
      (node (ref "U9") (pin "5") (pinfunction "OUT_5") (pintype "unspecified"))
    )
    (net (code "35") (name "unconnected-(U1-IO0-Pad18)") (class "Default")
      (node (ref "U1") (pin "18") (pinfunction "IO0_18") (pintype "unspecified+no_connect"))
    )
    (net (code "36") (name "unconnected-(U1-IO2-Pad16)") (class "Default")
      (node (ref "U1") (pin "16") (pinfunction "IO2_16") (pintype "unspecified+no_connect"))
    )
    (net (code "37") (name "unconnected-(U1-IO10-Pad10)") (class "Default")
      (node (ref "U1") (pin "10") (pinfunction "IO10_10") (pintype "unspecified+no_connect"))
    )
    (net (code "38") (name "unconnected-(U7-NC-Pad9)") (class "Default")
      (node (ref "U7") (pin "9") (pinfunction "NC_9") (pintype "unspecified+no_connect"))
    )
    (net (code "39") (name "unconnected-(U9-NC-Pad4)") (class "Default")
      (node (ref "U9") (pin "4") (pinfunction "NC_4") (pintype "unspecified+no_connect"))
    )
    (net (code "40") (name "unconnected-(U10-N{slash}C-Pad4)") (class "Default")
      (node (ref "U10") (pin "4") (pinfunction "N/C_4") (pintype "input+no_connect"))
    )
    (net (code "41") (name "unconnected-(USB1-SBU1-Pad9)") (class "Default")
      (node (ref "USB1") (pin "9") (pinfunction "SBU1_9") (pintype "unspecified+no_connect"))
    )
    (net (code "42") (name "unconnected-(USB1-SBU2-Pad3)") (class "Default")
      (node (ref "USB1") (pin "3") (pinfunction "SBU2_3") (pintype "unspecified+no_connect"))
    )
  )
)
